# projet_electronique.net
KiCad netlist of a schematic drawn in EAGLE
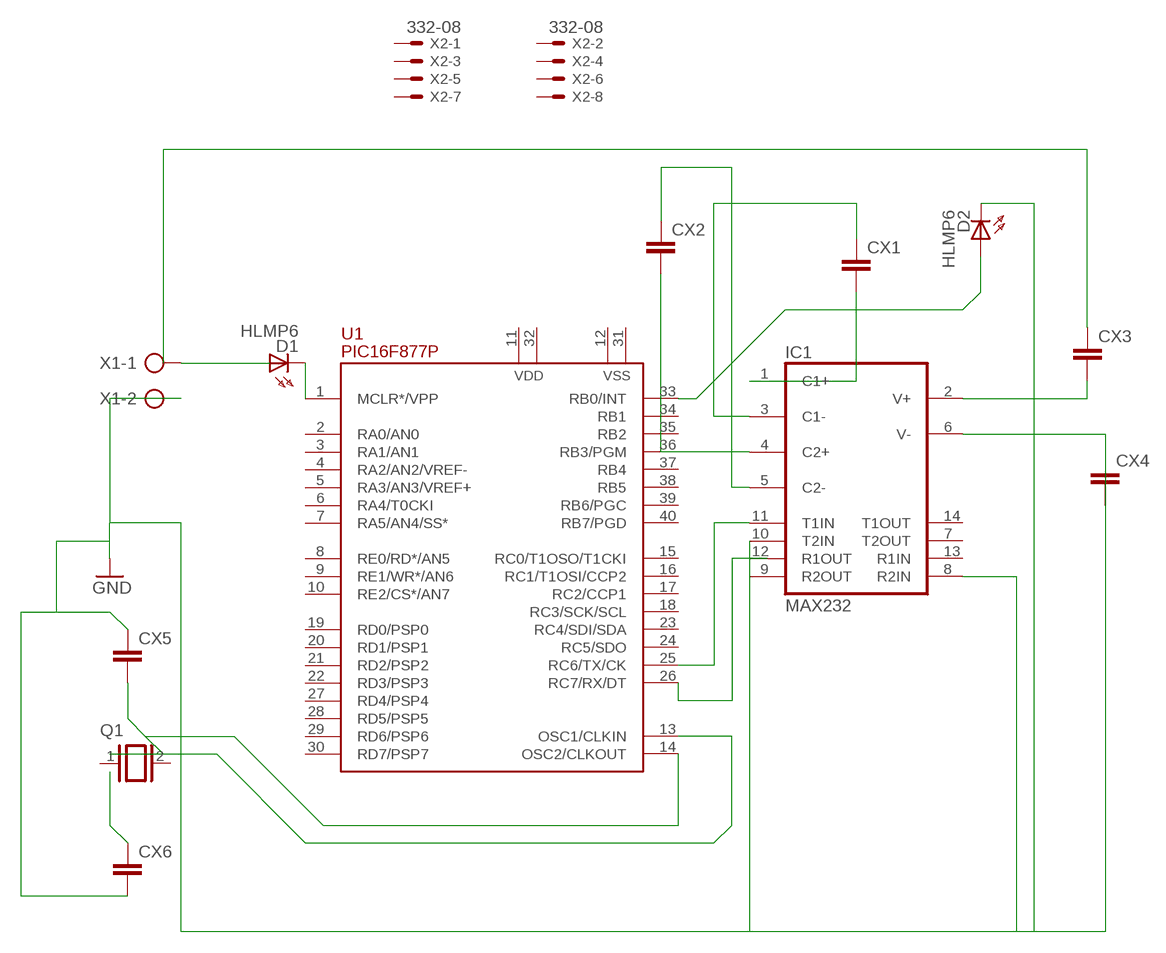
[diagram p0: schematic, sheet 1]

(export (version "E")
  (design (tool "Eeschema 10.0.6"))
  (components
    (comp (ref "CX1")
      (value "CXXC10B5")
      (footprint "eagle-import:XC10B5")
      (libsource (lib "eagle-import") (part "CXXC10B5"))
    )
    (comp (ref "CX2")
      (value "CXXC10B5")
      (footprint "eagle-import:XC10B5")
      (libsource (lib "eagle-import") (part "CXXC10B5"))
    )
    (comp (ref "CX3")
      (value "CXXC10B5")
      (footprint "eagle-import:XC10B5")
      (libsource (lib "eagle-import") (part "CXXC10B5"))
    )
    (comp (ref "CX4")
      (value "CXXC10B5")
      (footprint "eagle-import:XC10B5")
      (libsource (lib "eagle-import") (part "CXXC10B5"))
    )
    (comp (ref "CX5")
      (value "CXXC10B5")
      (footprint "eagle-import:XC10B5")
      (libsource (lib "eagle-import") (part "CXXC10B5"))
    )
    (comp (ref "CX6")
      (value "CXXC10B5")
      (footprint "eagle-import:XC10B5")
      (libsource (lib "eagle-import") (part "CXXC10B5"))
    )
    (comp (ref "D1")
      (value "HLMP6")
      (footprint "eagle-import:HLMP6")
      (fields (field (name "MF") "AGILENT TECHNOLOGIES") (field (name "MPN") "HLMP-6500"))
      (libsource (lib "eagle-import") (part "HLMP6"))
    )
    (comp (ref "D2")
      (value "HLMP6")
      (footprint "eagle-import:HLMP6")
      (fields (field (name "MF") "AGILENT TECHNOLOGIES") (field (name "MPN") "HLMP-6500"))
      (libsource (lib "eagle-import") (part "HLMP6"))
    )
    (comp (ref "IC1")
      (value "MAX232")
      (footprint "eagle-import:DIL16")
      (fields (field (name "MF") "MAXIM") (field (name "MPN") "MAX232ACPE+"))
      (libsource (lib "eagle-import") (part "MAX232"))
    )
    (comp (ref "Q1")
      (value "XTAL")
      (footprint "eagle-import:Q")
      (libsource (lib "eagle-import") (part "XTAL"))
    )
    (comp (ref "U1")
      (value "PIC16F877P")
      (footprint "eagle-import:DIL40")
      (libsource (lib "eagle-import") (part "PIC16F877P"))
    )
    (comp (ref "X1")
      (value "AK500/2-H")
      (footprint "eagle-import:AK500_2-H")
      (libsource (lib "eagle-import") (part "AK500/2-H"))
    )
    (comp (ref "X2")
      (value "332-08")
      (footprint "eagle-import:332-08")
      (libsource (lib "eagle-import") (part "332-08"))
    )
  )
  (nets
    (net (code "1") (name "GND") (class "Default")
      (node (ref "CX4") (pin "1") (pinfunction "1_1") (pintype "passive"))
      (node (ref "CX4") (pin "2") (pinfunction "2_2") (pintype "passive"))
      (node (ref "CX5") (pin "1") (pinfunction "1_1") (pintype "passive"))
      (node (ref "CX6") (pin "2") (pinfunction "2_2") (pintype "passive"))
      (node (ref "D2") (pin "K") (pinfunction "K_K") (pintype "passive"))
      (node (ref "IC1") (pin "10") (pinfunction "T2IN_10") (pintype "input"))
      (node (ref "IC1") (pin "6") (pinfunction "V-_6") (pintype "bidirectional"))
      (node (ref "IC1") (pin "8") (pinfunction "R2IN_8") (pintype "input"))
      (node (ref "X1") (pin "2") (pinfunction "KL_2") (pintype "passive"))
    )
    (net (code "2") (name "Net-(IC1A-C1+)") (class "Default")
      (node (ref "CX1") (pin "2") (pinfunction "2_2") (pintype "passive"))
      (node (ref "IC1") (pin "1") (pinfunction "C1+_1") (pintype "bidirectional"))
    )
    (net (code "3") (name "Net-(IC1A-C1-)") (class "Default")
      (node (ref "CX1") (pin "1") (pinfunction "1_1") (pintype "passive"))
      (node (ref "IC1") (pin "3") (pinfunction "C1-_3") (pintype "bidirectional"))
    )
    (net (code "4") (name "Net-(IC1A-C2+)") (class "Default")
      (node (ref "CX2") (pin "2") (pinfunction "2_2") (pintype "passive"))
      (node (ref "IC1") (pin "4") (pinfunction "C2+_4") (pintype "bidirectional"))
    )
    (net (code "5") (name "Net-(IC1A-C2-)") (class "Default")
      (node (ref "CX2") (pin "1") (pinfunction "1_1") (pintype "passive"))
      (node (ref "IC1") (pin "5") (pinfunction "C2-_5") (pintype "bidirectional"))
    )
    (net (code "6") (name "Net-(IC1A-T1IN)") (class "Default")
      (node (ref "IC1") (pin "11") (pinfunction "T1IN_11") (pintype "input"))
      (node (ref "U1") (pin "25") (pinfunction "RC6/TX/CK_25") (pintype "bidirectional"))
    )
    (net (code "7") (name "Net-(IC1A-V+)") (class "Default")
      (node (ref "CX3") (pin "2") (pinfunction "2_2") (pintype "passive"))
      (node (ref "IC1") (pin "2") (pinfunction "V+_2") (pintype "bidirectional"))
    )
    (net (code "8") (name "Net-(U1-MCLR*{slash}VPP)") (class "Default")
      (node (ref "D1") (pin "K") (pinfunction "K_K") (pintype "passive"))
      (node (ref "U1") (pin "1") (pinfunction "MCLR*/VPP_1") (pintype "input"))
    )
    (net (code "9") (name "Net-(U1-OSC1{slash}CLKIN)") (class "Default")
      (node (ref "CX5") (pin "2") (pinfunction "2_2") (pintype "passive"))
      (node (ref "U1") (pin "13") (pinfunction "OSC1/CLKIN_13") (pintype "input"))
      (node (ref "U1") (pin "14") (pinfunction "OSC2/CLKOUT_14") (pintype "output"))
    )
    (net (code "10") (name "Net-(U1-RB0{slash}INT)") (class "Default")
      (node (ref "D2") (pin "A") (pinfunction "A_A") (pintype "passive"))
      (node (ref "U1") (pin "33") (pinfunction "RB0/INT_33") (pintype "bidirectional"))
    )
    (net (code "11") (name "unconnected-(CX3-Pad1)") (class "Default")
      (node (ref "CX3") (pin "1") (pinfunction "1_1") (pintype "passive"))
    )
    (net (code "12") (name "unconnected-(CX6-Pad1)") (class "Default")
      (node (ref "CX6") (pin "1") (pinfunction "1_1") (pintype "passive"))
    )
    (net (code "13") (name "unconnected-(D1-PadA)") (class "Default")
      (node (ref "D1") (pin "A") (pinfunction "A_A") (pintype "passive"))
    )
    (net (code "14") (name "unconnected-(IC1A-R1IN-Pad13)") (class "Default")
      (node (ref "IC1") (pin "13") (pinfunction "R1IN_13") (pintype "input"))
    )
    (net (code "15") (name "unconnected-(IC1A-R1OUT-Pad12)") (class "Default")
      (node (ref "IC1") (pin "12") (pinfunction "R1OUT_12") (pintype "output"))
    )
    (net (code "16") (name "unconnected-(IC1A-R2OUT-Pad9)") (class "Default")
      (node (ref "IC1") (pin "9") (pinfunction "R2OUT_9") (pintype "output"))
    )
    (net (code "17") (name "unconnected-(IC1A-T1OUT-Pad14)") (class "Default")
      (node (ref "IC1") (pin "14") (pinfunction "T1OUT_14") (pintype "output"))
    )
    (net (code "18") (name "unconnected-(IC1A-T2OUT-Pad7)") (class "Default")
      (node (ref "IC1") (pin "7") (pinfunction "T2OUT_7") (pintype "output"))
    )
    (net (code "19") (name "unconnected-(Q1-Pad1)") (class "Default")
      (node (ref "Q1") (pin "1") (pinfunction "1_1") (pintype "passive"))
    )
    (net (code "20") (name "unconnected-(Q1-Pad2)") (class "Default")
      (node (ref "Q1") (pin "2") (pinfunction "2_2") (pintype "passive"))
    )
    (net (code "21") (name "unconnected-(U1-RA0{slash}AN0-Pad2)") (class "Default")
      (node (ref "U1") (pin "2") (pinfunction "RA0/AN0_2") (pintype "bidirectional"))
    )
    (net (code "22") (name "unconnected-(U1-RA1{slash}AN1-Pad3)") (class "Default")
      (node (ref "U1") (pin "3") (pinfunction "RA1/AN1_3") (pintype "bidirectional"))
    )
    (net (code "23") (name "unconnected-(U1-RA2{slash}AN2{slash}VREF--Pad4)") (class "Default")
      (node (ref "U1") (pin "4") (pinfunction "RA2/AN2/VREF-_4") (pintype "bidirectional"))
    )
    (net (code "24") (name "unconnected-(U1-RA3{slash}AN3{slash}VREF+-Pad5)") (class "Default")
      (node (ref "U1") (pin "5") (pinfunction "RA3/AN3/VREF+_5") (pintype "bidirectional"))
    )
    (net (code "25") (name "unconnected-(U1-RA4{slash}T0CKI-Pad6)") (class "Default")
      (node (ref "U1") (pin "6") (pinfunction "RA4/T0CKI_6") (pintype "bidirectional"))
    )
    (net (code "26") (name "unconnected-(U1-RA5{slash}AN4{slash}SS*-Pad7)") (class "Default")
      (node (ref "U1") (pin "7") (pinfunction "RA5/AN4/SS*_7") (pintype "bidirectional"))
    )
    (net (code "27") (name "unconnected-(U1-RB1-Pad34)") (class "Default")
      (node (ref "U1") (pin "34") (pinfunction "RB1_34") (pintype "bidirectional"))
    )
    (net (code "28") (name "unconnected-(U1-RB2-Pad35)") (class "Default")
      (node (ref "U1") (pin "35") (pinfunction "RB2_35") (pintype "bidirectional"))
    )
    (net (code "29") (name "unconnected-(U1-RB3{slash}PGM-Pad36)") (class "Default")
      (node (ref "U1") (pin "36") (pinfunction "RB3/PGM_36") (pintype "bidirectional"))
    )
    (net (code "30") (name "unconnected-(U1-RB4-Pad37)") (class "Default")
      (node (ref "U1") (pin "37") (pinfunction "RB4_37") (pintype "bidirectional"))
    )
    (net (code "31") (name "unconnected-(U1-RB5-Pad38)") (class "Default")
      (node (ref "U1") (pin "38") (pinfunction "RB5_38") (pintype "bidirectional"))
    )
    (net (code "32") (name "unconnected-(U1-RB6{slash}PGC-Pad39)") (class "Default")
      (node (ref "U1") (pin "39") (pinfunction "RB6/PGC_39") (pintype "bidirectional"))
    )
    (net (code "33") (name "unconnected-(U1-RB7{slash}PGD-Pad40)") (class "Default")
      (node (ref "U1") (pin "40") (pinfunction "RB7/PGD_40") (pintype "bidirectional"))
    )
    (net (code "34") (name "unconnected-(U1-RC0{slash}T1OSO{slash}T1CKI-Pad15)") (class "Default")
      (node (ref "U1") (pin "15") (pinfunction "RC0/T1OSO/T1CKI_15") (pintype "bidirectional"))
    )
    (net (code "35") (name "unconnected-(U1-RC1{slash}T1OSI{slash}CCP2-Pad16)") (class "Default")
      (node (ref "U1") (pin "16") (pinfunction "RC1/T1OSI/CCP2_16") (pintype "bidirectional"))
    )
    (net (code "36") (name "unconnected-(U1-RC2{slash}CCP1-Pad17)") (class "Default")
      (node (ref "U1") (pin "17") (pinfunction "RC2/CCP1_17") (pintype "bidirectional"))
    )
    (net (code "37") (name "unconnected-(U1-RC3{slash}SCK{slash}SCL-Pad18)") (class "Default")
      (node (ref "U1") (pin "18") (pinfunction "RC3/SCK/SCL_18") (pintype "bidirectional"))
    )
    (net (code "38") (name "unconnected-(U1-RC4{slash}SDI{slash}SDA-Pad23)") (class "Default")
      (node (ref "U1") (pin "23") (pinfunction "RC4/SDI/SDA_23") (pintype "bidirectional"))
    )
    (net (code "39") (name "unconnected-(U1-RC5{slash}SDO-Pad24)") (class "Default")
      (node (ref "U1") (pin "24") (pinfunction "RC5/SDO_24") (pintype "bidirectional"))
    )
    (net (code "40") (name "unconnected-(U1-RC7{slash}RX{slash}DT-Pad26)") (class "Default")
      (node (ref "U1") (pin "26") (pinfunction "RC7/RX/DT_26") (pintype "bidirectional"))
    )
    (net (code "41") (name "unconnected-(U1-RD0{slash}PSP0-Pad19)") (class "Default")
      (node (ref "U1") (pin "19") (pinfunction "RD0/PSP0_19") (pintype "bidirectional"))
    )
    (net (code "42") (name "unconnected-(U1-RD1{slash}PSP1-Pad20)") (class "Default")
      (node (ref "U1") (pin "20") (pinfunction "RD1/PSP1_20") (pintype "bidirectional"))
    )
    (net (code "43") (name "unconnected-(U1-RD2{slash}PSP2-Pad21)") (class "Default")
      (node (ref "U1") (pin "21") (pinfunction "RD2/PSP2_21") (pintype "bidirectional"))
    )
    (net (code "44") (name "unconnected-(U1-RD3{slash}PSP3-Pad22)") (class "Default")
      (node (ref "U1") (pin "22") (pinfunction "RD3/PSP3_22") (pintype "bidirectional"))
    )
    (net (code "45") (name "unconnected-(U1-RD4{slash}PSP4-Pad27)") (class "Default")
      (node (ref "U1") (pin "27") (pinfunction "RD4/PSP4_27") (pintype "bidirectional"))
    )
    (net (code "46") (name "unconnected-(U1-RD5{slash}PSP5-Pad28)") (class "Default")
      (node (ref "U1") (pin "28") (pinfunction "RD5/PSP5_28") (pintype "bidirectional"))
    )
    (net (code "47") (name "unconnected-(U1-RD6{slash}PSP6-Pad29)") (class "Default")
      (node (ref "U1") (pin "29") (pinfunction "RD6/PSP6_29") (pintype "bidirectional"))
    )
    (net (code "48") (name "unconnected-(U1-RD7{slash}PSP7-Pad30)") (class "Default")
      (node (ref "U1") (pin "30") (pinfunction "RD7/PSP7_30") (pintype "bidirectional"))
    )
    (net (code "49") (name "unconnected-(U1-RE0{slash}RD*{slash}AN5-Pad8)") (class "Default")
      (node (ref "U1") (pin "8") (pinfunction "RE0/RD*/AN5_8") (pintype "bidirectional"))
    )
    (net (code "50") (name "unconnected-(U1-RE1{slash}WR*{slash}AN6-Pad9)") (class "Default")
      (node (ref "U1") (pin "9") (pinfunction "RE1/WR*/AN6_9") (pintype "bidirectional"))
    )
    (net (code "51") (name "unconnected-(U1-RE2{slash}CS*{slash}AN7-Pad10)") (class "Default")
      (node (ref "U1") (pin "10") (pinfunction "RE2/CS*/AN7_10") (pintype "bidirectional"))
    )
    (net (code "52") (name "unconnected-(U1-VDD-Pad11)") (class "Default")
      (node (ref "U1") (pin "11") (pinfunction "VDD_11") (pintype "bidirectional"))
    )
    (net (code "53") (name "unconnected-(U1-VDD-Pad32)") (class "Default")
      (node (ref "U1") (pin "32") (pinfunction "VDD_32") (pintype "bidirectional"))
    )
    (net (code "54") (name "unconnected-(U1-VSS-Pad12)") (class "Default")
      (node (ref "U1") (pin "12") (pinfunction "VSS_12") (pintype "bidirectional"))
    )
    (net (code "55") (name "unconnected-(U1-VSS-Pad31)") (class "Default")
      (node (ref "U1") (pin "31") (pinfunction "VSS_31") (pintype "bidirectional"))
    )
    (net (code "56") (name "unconnected-(X1A-KL-Pad1)") (class "Default")
      (node (ref "X1") (pin "1") (pinfunction "KL_1") (pintype "passive"))
    )
    (net (code "57") (name "unconnected-(X2A-S-Pad1)") (class "Default")
      (node (ref "X2") (pin "1") (pinfunction "S_1") (pintype "passive"))
    )
    (net (code "58") (name "unconnected-(X2B-S-Pad2)") (class "Default")
      (node (ref "X2") (pin "2") (pinfunction "S_2") (pintype "passive"))
    )
    (net (code "59") (name "unconnected-(X2C-S-Pad3)") (class "Default")
      (node (ref "X2") (pin "3") (pinfunction "S_3") (pintype "passive"))
    )
    (net (code "60") (name "unconnected-(X2D-S-Pad4)") (class "Default")
      (node (ref "X2") (pin "4") (pinfunction "S_4") (pintype "passive"))
    )
    (net (code "61") (name "unconnected-(X2E-S-Pad5)") (class "Default")
      (node (ref "X2") (pin "5") (pinfunction "S_5") (pintype "passive"))
    )
    (net (code "62") (name "unconnected-(X2F-S-Pad6)") (class "Default")
      (node (ref "X2") (pin "6") (pinfunction "S_6") (pintype "passive"))
    )
    (net (code "63") (name "unconnected-(X2G-S-Pad7)") (class "Default")
      (node (ref "X2") (pin "7") (pinfunction "S_7") (pintype "passive"))
    )
    (net (code "64") (name "unconnected-(X2H-S-Pad8)") (class "Default")
      (node (ref "X2") (pin "8") (pinfunction "S_8") (pintype "passive"))
    )
  )
)
